# TU_MCU.net
KiCad netlist of a schematic drawn in Altium Designer
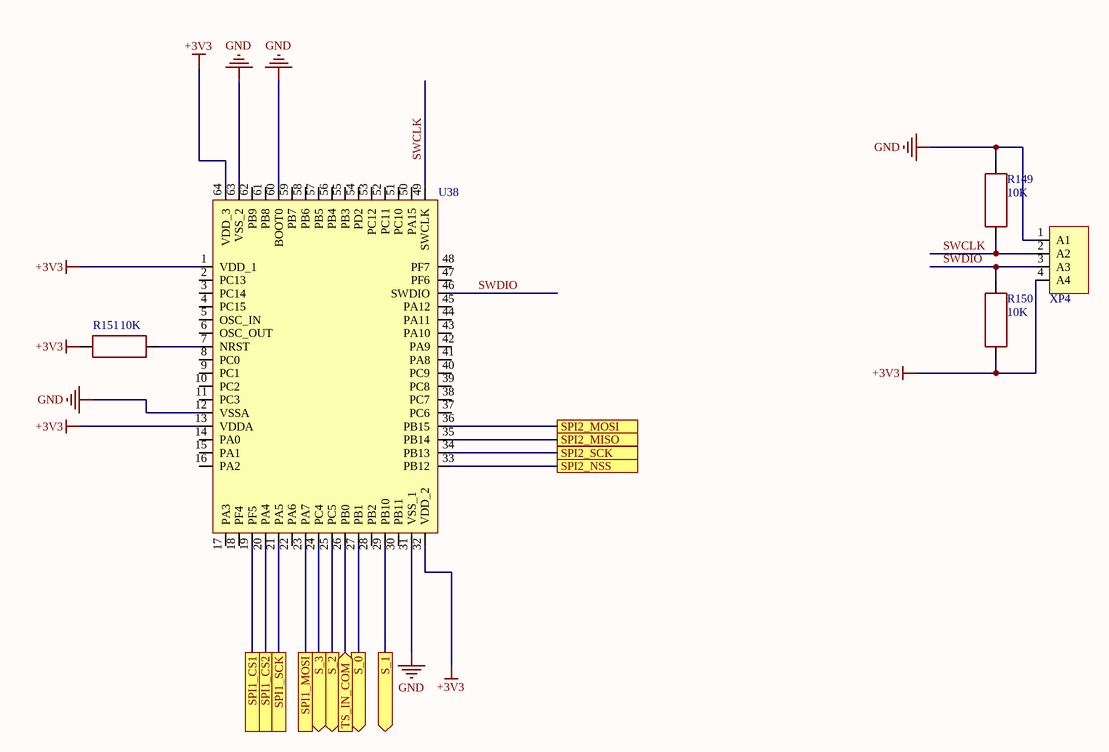
[diagram p0: TU_MCU.SchDoc]

(export (version "E")
  (design (tool "Eeschema 10.0.6"))
  (components
    (comp (ref "R149")
      (value "10K")
      (footprint "RES: 0603")
      (fields
        (field (name "POWER") "0.1W")
        (field (name "TOLERANCE") "±1%")
        (field (name "Comment") "Resistor_0603")
      )
      (libsource (lib "resistor") (part "Resistor_0603"))
    )
    (comp (ref "R150")
      (value "10K")
      (footprint "RES: 0603")
      (fields
        (field (name "POWER") "0.1W")
        (field (name "TOLERANCE") "±1%")
        (field (name "Comment") "Resistor_0603")
      )
      (libsource (lib "resistor") (part "Resistor_0603"))
    )
    (comp (ref "R151")
      (value "10K")
      (footprint "RES: 0603")
      (fields
        (field (name "POWER") "0.1W")
        (field (name "TOLERANCE") "±1%")
        (field (name "Comment") "Resistor_0603")
      )
      (libsource (lib "") (part "Resistor_0603_1"))
    )
    (comp (ref "U38")
      (value "STM32F030R8T6TR")
      (footprint "LQFP-64")
      (description "MCU Mainstream Arm Cortex-M0 Value line MCU 64 Kbytes of Flash , 48 MHz CPU")
      (fields (field (name "MANUFACTURER") "STMicroelectronics"))
      (libsource (lib "MY_INT_LIB") (part "STM32F030R8T6TR"))
    )
    (comp (ref "XP4")
      (value "PLS-6 (DS1021-1x6)")
      (footprint "PLS-4 (DS1021-1x4)")
      (description "Board to Board, Surface Mount, Single row, 6 Positions, 2.54mm, Vertical.")
      (fields (field (name "MANUFACTURER") "Connfly"))
      (libsource (lib "MY_INT_LIB") (part "PLS-4 (DS1021-1x4)"))
    )
  )
  (nets
    (net (code "1") (name "+3V3") (class "Default")
      (node (ref "R150") (pin "2") (pinfunction "2_2") (pintype "passive"))
      (node (ref "R151") (pin "1") (pinfunction "1_1") (pintype "passive"))
      (node (ref "U38") (pin "1") (pinfunction "VDD_1_1") (pintype "power_in"))
      (node (ref "U38") (pin "13") (pinfunction "VDDA_13") (pintype "power_in"))
      (node (ref "U38") (pin "32") (pinfunction "VDD_2_32") (pintype "power_in"))
      (node (ref "U38") (pin "64") (pinfunction "VDD_3_64") (pintype "power_in"))
      (node (ref "XP4") (pin "4") (pinfunction "A4_4") (pintype "passive"))
    )
    (net (code "2") (name "/SPI1_CS1") (class "Default")
      (node (ref "U38") (pin "19") (pinfunction "PF5_19") (pintype "passive"))
    )
    (net (code "3") (name "/SPI1_CS2") (class "Default")
      (node (ref "U38") (pin "20") (pinfunction "PA4_20") (pintype "passive"))
    )
    (net (code "4") (name "/SPI1_MOSI") (class "Default")
      (node (ref "U38") (pin "23") (pinfunction "PA7_23") (pintype "passive"))
    )
    (net (code "5") (name "/SPI1_SCK") (class "Default")
      (node (ref "U38") (pin "21") (pinfunction "PA5_21") (pintype "passive"))
    )
    (net (code "6") (name "/SPI2_MISO") (class "Default")
      (node (ref "U38") (pin "35") (pinfunction "PB14_35") (pintype "passive"))
    )
    (net (code "7") (name "/SPI2_MOSI") (class "Default")
      (node (ref "U38") (pin "36") (pinfunction "PB15_36") (pintype "passive"))
    )
    (net (code "8") (name "/SPI2_NSS") (class "Default")
      (node (ref "U38") (pin "33") (pinfunction "PB12_33") (pintype "passive"))
    )
    (net (code "9") (name "/SPI2_SCK") (class "Default")
      (node (ref "U38") (pin "34") (pinfunction "PB13_34") (pintype "passive"))
    )
    (net (code "10") (name "/SWCLK") (class "Default")
      (node (ref "R149") (pin "2") (pinfunction "2_2") (pintype "passive"))
      (node (ref "U38") (pin "49") (pinfunction "SWCLK_49") (pintype "passive"))
      (node (ref "XP4") (pin "2") (pinfunction "A2_2") (pintype "passive"))
    )
    (net (code "11") (name "/SWDIO") (class "Default")
      (node (ref "R150") (pin "1") (pinfunction "1_1") (pintype "passive"))
      (node (ref "U38") (pin "46") (pinfunction "SWDIO_46") (pintype "passive"))
      (node (ref "XP4") (pin "3") (pinfunction "A3_3") (pintype "passive"))
    )
    (net (code "12") (name "/S_0") (class "Default")
      (node (ref "U38") (pin "27") (pinfunction "PB1_27") (pintype "passive"))
    )
    (net (code "13") (name "/S_1") (class "Default")
      (node (ref "U38") (pin "29") (pinfunction "PB10_29") (pintype "passive"))
    )
    (net (code "14") (name "/S_2") (class "Default")
      (node (ref "U38") (pin "25") (pinfunction "PC5_25") (pintype "passive"))
    )
    (net (code "15") (name "/S_3") (class "Default")
      (node (ref "U38") (pin "24") (pinfunction "PC4_24") (pintype "passive"))
    )
    (net (code "16") (name "/TS_IN_COM") (class "Default")
      (node (ref "U38") (pin "26") (pinfunction "PB0_26") (pintype "passive"))
    )
    (net (code "17") (name "GND") (class "Default")
      (node (ref "R149") (pin "1") (pinfunction "1_1") (pintype "passive"))
      (node (ref "U38") (pin "12") (pinfunction "VSSA_12") (pintype "power_in"))
      (node (ref "U38") (pin "31") (pinfunction "VSS_1_31") (pintype "power_in"))
      (node (ref "U38") (pin "60") (pinfunction "BOOT0_60") (pintype "passive"))
      (node (ref "U38") (pin "63") (pinfunction "VSS_2_63") (pintype "power_in"))
      (node (ref "XP4") (pin "1") (pinfunction "A1_1") (pintype "passive"))
    )
    (net (code "18") (name "Net-(U38-NRST)") (class "Default")
      (node (ref "R151") (pin "2") (pinfunction "2_2") (pintype "passive"))
      (node (ref "U38") (pin "7") (pinfunction "NRST_7") (pintype "passive"))
    )
    (net (code "19") (name "unconnected-(U38-OSC_IN-Pad5)") (class "Default")
      (node (ref "U38") (pin "5") (pinfunction "OSC_IN_5") (pintype "passive"))
    )
    (net (code "20") (name "unconnected-(U38-OSC_OUT-Pad6)") (class "Default")
      (node (ref "U38") (pin "6") (pinfunction "OSC_OUT_6") (pintype "passive"))
    )
    (net (code "21") (name "unconnected-(U38-PA0-Pad14)") (class "Default")
      (node (ref "U38") (pin "14") (pinfunction "PA0_14") (pintype "passive"))
    )
    (net (code "22") (name "unconnected-(U38-PA1-Pad15)") (class "Default")
      (node (ref "U38") (pin "15") (pinfunction "PA1_15") (pintype "passive"))
    )
    (net (code "23") (name "unconnected-(U38-PA2-Pad16)") (class "Default")
      (node (ref "U38") (pin "16") (pinfunction "PA2_16") (pintype "passive"))
    )
    (net (code "24") (name "unconnected-(U38-PA3-Pad17)") (class "Default")
      (node (ref "U38") (pin "17") (pinfunction "PA3_17") (pintype "passive"))
    )
    (net (code "25") (name "unconnected-(U38-PA6-Pad22)") (class "Default")
      (node (ref "U38") (pin "22") (pinfunction "PA6_22") (pintype "passive"))
    )
    (net (code "26") (name "unconnected-(U38-PA8-Pad41)") (class "Default")
      (node (ref "U38") (pin "41") (pinfunction "PA8_41") (pintype "passive"))
    )
    (net (code "27") (name "unconnected-(U38-PA9-Pad42)") (class "Default")
      (node (ref "U38") (pin "42") (pinfunction "PA9_42") (pintype "passive"))
    )
    (net (code "28") (name "unconnected-(U38-PA10-Pad43)") (class "Default")
      (node (ref "U38") (pin "43") (pinfunction "PA10_43") (pintype "passive"))
    )
    (net (code "29") (name "unconnected-(U38-PA11-Pad44)") (class "Default")
      (node (ref "U38") (pin "44") (pinfunction "PA11_44") (pintype "passive"))
    )
    (net (code "30") (name "unconnected-(U38-PA12-Pad45)") (class "Default")
      (node (ref "U38") (pin "45") (pinfunction "PA12_45") (pintype "passive"))
    )
    (net (code "31") (name "unconnected-(U38-PA15-Pad50)") (class "Default")
      (node (ref "U38") (pin "50") (pinfunction "PA15_50") (pintype "passive"))
    )
    (net (code "32") (name "unconnected-(U38-PB2-Pad28)") (class "Default")
      (node (ref "U38") (pin "28") (pinfunction "PB2_28") (pintype "passive"))
    )
    (net (code "33") (name "unconnected-(U38-PB3-Pad55)") (class "Default")
      (node (ref "U38") (pin "55") (pinfunction "PB3_55") (pintype "passive"))
    )
    (net (code "34") (name "unconnected-(U38-PB4-Pad56)") (class "Default")
      (node (ref "U38") (pin "56") (pinfunction "PB4_56") (pintype "passive"))
    )
    (net (code "35") (name "unconnected-(U38-PB5-Pad57)") (class "Default")
      (node (ref "U38") (pin "57") (pinfunction "PB5_57") (pintype "passive"))
    )
    (net (code "36") (name "unconnected-(U38-PB6-Pad58)") (class "Default")
      (node (ref "U38") (pin "58") (pinfunction "PB6_58") (pintype "passive"))
    )
    (net (code "37") (name "unconnected-(U38-PB7-Pad59)") (class "Default")
      (node (ref "U38") (pin "59") (pinfunction "PB7_59") (pintype "passive"))
    )
    (net (code "38") (name "unconnected-(U38-PB8-Pad61)") (class "Default")
      (node (ref "U38") (pin "61") (pinfunction "PB8_61") (pintype "passive"))
    )
    (net (code "39") (name "unconnected-(U38-PB9-Pad62)") (class "Default")
      (node (ref "U38") (pin "62") (pinfunction "PB9_62") (pintype "passive"))
    )
    (net (code "40") (name "unconnected-(U38-PB11-Pad30)") (class "Default")
      (node (ref "U38") (pin "30") (pinfunction "PB11_30") (pintype "passive"))
    )
    (net (code "41") (name "unconnected-(U38-PC0-Pad8)") (class "Default")
      (node (ref "U38") (pin "8") (pinfunction "PC0_8") (pintype "passive"))
    )
    (net (code "42") (name "unconnected-(U38-PC1-Pad9)") (class "Default")
      (node (ref "U38") (pin "9") (pinfunction "PC1_9") (pintype "passive"))
    )
    (net (code "43") (name "unconnected-(U38-PC2-Pad10)") (class "Default")
      (node (ref "U38") (pin "10") (pinfunction "PC2_10") (pintype "passive"))
    )
    (net (code "44") (name "unconnected-(U38-PC3-Pad11)") (class "Default")
      (node (ref "U38") (pin "11") (pinfunction "PC3_11") (pintype "passive"))
    )
    (net (code "45") (name "unconnected-(U38-PC6-Pad37)") (class "Default")
      (node (ref "U38") (pin "37") (pinfunction "PC6_37") (pintype "passive"))
    )
    (net (code "46") (name "unconnected-(U38-PC7-Pad38)") (class "Default")
      (node (ref "U38") (pin "38") (pinfunction "PC7_38") (pintype "passive"))
    )
    (net (code "47") (name "unconnected-(U38-PC8-Pad39)") (class "Default")
      (node (ref "U38") (pin "39") (pinfunction "PC8_39") (pintype "passive"))
    )
    (net (code "48") (name "unconnected-(U38-PC9-Pad40)") (class "Default")
      (node (ref "U38") (pin "40") (pinfunction "PC9_40") (pintype "passive"))
    )
    (net (code "49") (name "unconnected-(U38-PC10-Pad51)") (class "Default")
      (node (ref "U38") (pin "51") (pinfunction "PC10_51") (pintype "passive"))
    )
    (net (code "50") (name "unconnected-(U38-PC11-Pad52)") (class "Default")
      (node (ref "U38") (pin "52") (pinfunction "PC11_52") (pintype "passive"))
    )
    (net (code "51") (name "unconnected-(U38-PC12-Pad53)") (class "Default")
      (node (ref "U38") (pin "53") (pinfunction "PC12_53") (pintype "passive"))
    )
    (net (code "52") (name "unconnected-(U38-PC13-Pad2)") (class "Default")
      (node (ref "U38") (pin "2") (pinfunction "PC13_2") (pintype "passive"))
    )
    (net (code "53") (name "unconnected-(U38-PC14-Pad3)") (class "Default")
      (node (ref "U38") (pin "3") (pinfunction "PC14_3") (pintype "passive"))
    )
    (net (code "54") (name "unconnected-(U38-PC15-Pad4)") (class "Default")
      (node (ref "U38") (pin "4") (pinfunction "PC15_4") (pintype "passive"))
    )
    (net (code "55") (name "unconnected-(U38-PD2-Pad54)") (class "Default")
      (node (ref "U38") (pin "54") (pinfunction "PD2_54") (pintype "passive"))
    )
    (net (code "56") (name "unconnected-(U38-PF4-Pad18)") (class "Default")
      (node (ref "U38") (pin "18") (pinfunction "PF4_18") (pintype "passive"))
    )
    (net (code "57") (name "unconnected-(U38-PF6-Pad47)") (class "Default")
      (node (ref "U38") (pin "47") (pinfunction "PF6_47") (pintype "passive"))
    )
    (net (code "58") (name "unconnected-(U38-PF7-Pad48)") (class "Default")
      (node (ref "U38") (pin "48") (pinfunction "PF7_48") (pintype "passive"))
    )
  )
)
